# diy_mainboard.net
KiCad netlist of a schematic drawn in EAGLE
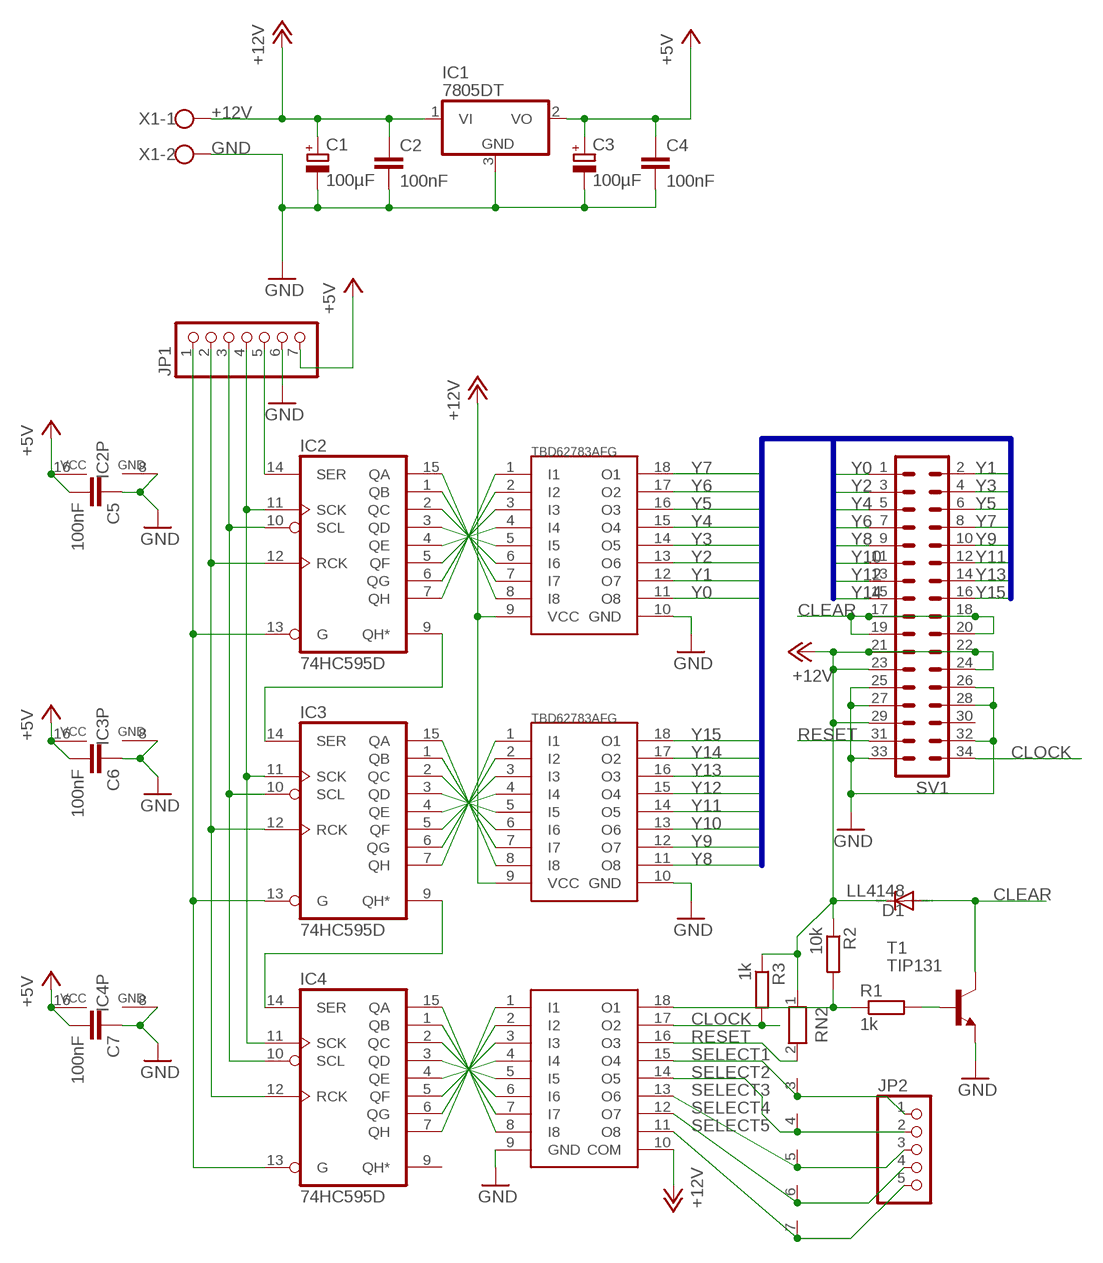
[diagram p0: schematic, sheet 1]

(export (version "E")
  (design (tool "Eeschema 10.0.6"))
  (components
    (comp (ref "C1")
      (value "100µF")
      (footprint "eagle-import:153CLV-0605")
      (libsource (lib "eagle-import") (part "CPOL-EU153CLV-0605"))
    )
    (comp (ref "C2")
      (value "100nF")
      (footprint "eagle-import:C0603")
      (libsource (lib "eagle-import") (part "C-EUC0603"))
    )
    (comp (ref "C3")
      (value "100µF")
      (footprint "eagle-import:153CLV-0605")
      (libsource (lib "eagle-import") (part "CPOL-EU153CLV-0605"))
    )
    (comp (ref "C4")
      (value "100nF")
      (footprint "eagle-import:C0603")
      (libsource (lib "eagle-import") (part "C-EUC0603"))
    )
    (comp (ref "C5")
      (value "100nF")
      (footprint "eagle-import:C0603")
      (libsource (lib "eagle-import") (part "C-EUC0603"))
    )
    (comp (ref "C6")
      (value "100nF")
      (footprint "eagle-import:C0603")
      (libsource (lib "eagle-import") (part "C-EUC0603"))
    )
    (comp (ref "C7")
      (value "100nF")
      (footprint "eagle-import:C0603")
      (libsource (lib "eagle-import") (part "C-EUC0603"))
    )
    (comp (ref "D1")
      (value "LL4148")
      (footprint "eagle-import:SOD80C")
      (libsource (lib "eagle-import") (part "PMLL4150"))
    )
    (comp (ref "IC1")
      (value "7805DT")
      (footprint "eagle-import:TO252")
      (libsource (lib "eagle-import") (part "78DT05"))
    )
    (comp (ref "IC2")
      (value "74HC595D")
      (footprint "eagle-import:SO16")
      (fields (field (name "DIGIKEY") "568-2263-1-ND"))
      (libsource (lib "eagle-import") (part "74595DHC"))
    )
    (comp (ref "IC3")
      (value "74HC595D")
      (footprint "eagle-import:SO16")
      (fields (field (name "DIGIKEY") "568-2263-1-ND"))
      (libsource (lib "eagle-import") (part "74595DHC"))
    )
    (comp (ref "IC4")
      (value "74HC595D")
      (footprint "eagle-import:SO16")
      (fields (field (name "DIGIKEY") "568-2263-1-ND"))
      (libsource (lib "eagle-import") (part "74595DHC"))
    )
    (comp (ref "JP1")
      (value "PINHD-1X7")
      (footprint "eagle-import:1X07")
      (libsource (lib "eagle-import") (part "PINHD-1X7"))
    )
    (comp (ref "JP2")
      (value "PINHD-1X5")
      (footprint "eagle-import:1X05")
      (libsource (lib "eagle-import") (part "PINHD-1X5"))
    )
    (comp (ref "R1")
      (value "1k")
      (footprint "eagle-import:R0805")
      (libsource (lib "eagle-import") (part "R-EU_R0805"))
    )
    (comp (ref "R2")
      (value "10k")
      (footprint "eagle-import:R0805")
      (libsource (lib "eagle-import") (part "R-EU_R0805"))
    )
    (comp (ref "R3")
      (value "1k")
      (footprint "eagle-import:R0805")
      (libsource (lib "eagle-import") (part "R-EU_R0805"))
    )
    (comp (ref "RN2")
      (value "RN06")
      (footprint "eagle-import:RN-7")
      (libsource (lib "eagle-import") (part "RN06"))
    )
    (comp (ref "SV1")
      (value "ML34")
      (footprint "eagle-import:ML34")
      (libsource (lib "eagle-import") (part "ML34"))
    )
    (comp (ref "T1")
      (value "TIP131")
      (footprint "eagle-import:TO220BV")
      (libsource (lib "eagle-import") (part "2SC1306"))
    )
    (comp (ref "U$1")
      (value "TBD62783AFG")
      (footprint "eagle-import:SO8-L")
      (libsource (lib "eagle-import") (part "TBD62783AFG"))
    )
    (comp (ref "U$2")
      (value "TBD62783AFG")
      (footprint "eagle-import:SO8-L")
      (libsource (lib "eagle-import") (part "TBD62783AFG"))
    )
    (comp (ref "U$3")
      (value "ULN2803")
      (footprint "eagle-import:SO8-L")
      (libsource (lib "eagle-import") (part "ULN2803"))
    )
    (comp (ref "X1")
      (value "W237-102")
      (footprint "eagle-import:W237-102")
      (fields (field (name "MPN") "237-102"))
      (libsource (lib "eagle-import") (part "W237-102"))
    )
  )
  (nets
    (net (code "1") (name "+5V") (class "Default")
      (node (ref "C3") (pin "+") (pinfunction "+_+") (pintype "passive"))
      (node (ref "C4") (pin "1") (pinfunction "1_1") (pintype "passive"))
      (node (ref "C5") (pin "2") (pinfunction "2_2") (pintype "passive"))
      (node (ref "C6") (pin "2") (pinfunction "2_2") (pintype "passive"))
      (node (ref "C7") (pin "2") (pinfunction "2_2") (pintype "passive"))
      (node (ref "IC1") (pin "2") (pinfunction "VO_2") (pintype "passive"))
      (node (ref "IC2") (pin "16") (pinfunction "VCC_16") (pintype "power_in"))
      (node (ref "IC3") (pin "16") (pinfunction "VCC_16") (pintype "power_in"))
      (node (ref "IC4") (pin "16") (pinfunction "VCC_16") (pintype "power_in"))
      (node (ref "JP1") (pin "7") (pinfunction "7_7") (pintype "passive"))
    )
    (net (code "2") (name "+12V") (class "Default")
      (node (ref "C1") (pin "+") (pinfunction "+_+") (pintype "passive"))
      (node (ref "C2") (pin "1") (pinfunction "1_1") (pintype "passive"))
      (node (ref "D1") (pin "C") (pinfunction "C_C") (pintype "passive"))
      (node (ref "IC1") (pin "1") (pinfunction "VI_1") (pintype "input"))
      (node (ref "R2") (pin "1") (pinfunction "1_1") (pintype "passive"))
      (node (ref "R3") (pin "1") (pinfunction "1_1") (pintype "passive"))
      (node (ref "RN2") (pin "1") (pinfunction "1_1") (pintype "passive"))
      (node (ref "SV1") (pin "21") (pinfunction "21_21") (pintype "passive"))
      (node (ref "SV1") (pin "22") (pinfunction "22_22") (pintype "passive"))
      (node (ref "SV1") (pin "23") (pinfunction "23_23") (pintype "passive"))
      (node (ref "SV1") (pin "24") (pinfunction "24_24") (pintype "passive"))
      (node (ref "SV1") (pin "29") (pinfunction "29_29") (pintype "passive"))
      (node (ref "U$1") (pin "9") (pinfunction "VCC_9") (pintype "bidirectional"))
      (node (ref "U$2") (pin "9") (pinfunction "VCC_9") (pintype "bidirectional"))
      (node (ref "U$3") (pin "10") (pinfunction "COM_10") (pintype "bidirectional"))
      (node (ref "X1") (pin "1") (pinfunction "KL_1") (pintype "passive"))
    )
    (net (code "3") (name "/CLEAR") (class "Default")
      (node (ref "D1") (pin "A") (pinfunction "A_A") (pintype "passive"))
      (node (ref "SV1") (pin "17") (pinfunction "17_17") (pintype "passive"))
      (node (ref "SV1") (pin "18") (pinfunction "18_18") (pintype "passive"))
      (node (ref "SV1") (pin "19") (pinfunction "19_19") (pintype "passive"))
      (node (ref "SV1") (pin "20") (pinfunction "20_20") (pintype "passive"))
      (node (ref "T1") (pin "2") (pinfunction "C_2") (pintype "passive"))
    )
    (net (code "4") (name "/CLOCK") (class "Default")
      (node (ref "R3") (pin "2") (pinfunction "2_2") (pintype "passive"))
      (node (ref "SV1") (pin "34") (pinfunction "34_34") (pintype "passive"))
      (node (ref "U$3") (pin "17") (pinfunction "O2_17") (pintype "bidirectional"))
    )
    (net (code "5") (name "/RESET") (class "Default")
      (node (ref "RN2") (pin "2") (pinfunction "2_2") (pintype "passive"))
      (node (ref "SV1") (pin "31") (pinfunction "31_31") (pintype "passive"))
      (node (ref "U$3") (pin "16") (pinfunction "O3_16") (pintype "bidirectional"))
    )
    (net (code "6") (name "/SELECT1") (class "Default")
      (node (ref "JP2") (pin "1") (pinfunction "1_1") (pintype "passive"))
      (node (ref "RN2") (pin "3") (pinfunction "3_3") (pintype "passive"))
      (node (ref "U$3") (pin "15") (pinfunction "O4_15") (pintype "bidirectional"))
    )
    (net (code "7") (name "/SELECT2") (class "Default")
      (node (ref "JP2") (pin "2") (pinfunction "2_2") (pintype "passive"))
      (node (ref "RN2") (pin "4") (pinfunction "4_4") (pintype "passive"))
      (node (ref "U$3") (pin "14") (pinfunction "O5_14") (pintype "bidirectional"))
    )
    (net (code "8") (name "/SELECT3") (class "Default")
      (node (ref "JP2") (pin "3") (pinfunction "3_3") (pintype "passive"))
      (node (ref "RN2") (pin "5") (pinfunction "5_5") (pintype "passive"))
      (node (ref "U$3") (pin "13") (pinfunction "O6_13") (pintype "bidirectional"))
    )
    (net (code "9") (name "/SELECT4") (class "Default")
      (node (ref "JP2") (pin "4") (pinfunction "4_4") (pintype "passive"))
      (node (ref "RN2") (pin "6") (pinfunction "6_6") (pintype "passive"))
      (node (ref "U$3") (pin "12") (pinfunction "O7_12") (pintype "bidirectional"))
    )
    (net (code "10") (name "/SELECT5") (class "Default")
      (node (ref "JP2") (pin "5") (pinfunction "5_5") (pintype "passive"))
      (node (ref "RN2") (pin "7") (pinfunction "7_7") (pintype "passive"))
      (node (ref "U$3") (pin "11") (pinfunction "O8_11") (pintype "bidirectional"))
    )
    (net (code "11") (name "/Y0") (class "Default")
      (node (ref "SV1") (pin "1") (pinfunction "1_1") (pintype "passive"))
      (node (ref "U$1") (pin "11") (pinfunction "O8_11") (pintype "bidirectional"))
    )
    (net (code "12") (name "/Y1") (class "Default")
      (node (ref "SV1") (pin "2") (pinfunction "2_2") (pintype "passive"))
      (node (ref "U$1") (pin "12") (pinfunction "O7_12") (pintype "bidirectional"))
    )
    (net (code "13") (name "/Y2") (class "Default")
      (node (ref "SV1") (pin "3") (pinfunction "3_3") (pintype "passive"))
      (node (ref "U$1") (pin "13") (pinfunction "O6_13") (pintype "bidirectional"))
    )
    (net (code "14") (name "/Y3") (class "Default")
      (node (ref "SV1") (pin "4") (pinfunction "4_4") (pintype "passive"))
      (node (ref "U$1") (pin "14") (pinfunction "O5_14") (pintype "bidirectional"))
    )
    (net (code "15") (name "/Y4") (class "Default")
      (node (ref "SV1") (pin "5") (pinfunction "5_5") (pintype "passive"))
      (node (ref "U$1") (pin "15") (pinfunction "O4_15") (pintype "bidirectional"))
    )
    (net (code "16") (name "/Y5") (class "Default")
      (node (ref "SV1") (pin "6") (pinfunction "6_6") (pintype "passive"))
      (node (ref "U$1") (pin "16") (pinfunction "O3_16") (pintype "bidirectional"))
    )
    (net (code "17") (name "/Y6") (class "Default")
      (node (ref "SV1") (pin "7") (pinfunction "7_7") (pintype "passive"))
      (node (ref "U$1") (pin "17") (pinfunction "O2_17") (pintype "bidirectional"))
    )
    (net (code "18") (name "/Y7") (class "Default")
      (node (ref "SV1") (pin "8") (pinfunction "8_8") (pintype "passive"))
      (node (ref "U$1") (pin "18") (pinfunction "O1_18") (pintype "bidirectional"))
    )
    (net (code "19") (name "/Y8") (class "Default")
      (node (ref "SV1") (pin "9") (pinfunction "9_9") (pintype "passive"))
      (node (ref "U$2") (pin "11") (pinfunction "O8_11") (pintype "bidirectional"))
    )
    (net (code "20") (name "/Y9") (class "Default")
      (node (ref "SV1") (pin "10") (pinfunction "10_10") (pintype "passive"))
      (node (ref "U$2") (pin "12") (pinfunction "O7_12") (pintype "bidirectional"))
    )
    (net (code "21") (name "/Y10") (class "Default")
      (node (ref "SV1") (pin "11") (pinfunction "11_11") (pintype "passive"))
      (node (ref "U$2") (pin "13") (pinfunction "O6_13") (pintype "bidirectional"))
    )
    (net (code "22") (name "/Y11") (class "Default")
      (node (ref "SV1") (pin "12") (pinfunction "12_12") (pintype "passive"))
      (node (ref "U$2") (pin "14") (pinfunction "O5_14") (pintype "bidirectional"))
    )
    (net (code "23") (name "/Y12") (class "Default")
      (node (ref "SV1") (pin "13") (pinfunction "13_13") (pintype "passive"))
      (node (ref "U$2") (pin "15") (pinfunction "O4_15") (pintype "bidirectional"))
    )
    (net (code "24") (name "/Y13") (class "Default")
      (node (ref "SV1") (pin "14") (pinfunction "14_14") (pintype "passive"))
      (node (ref "U$2") (pin "16") (pinfunction "O3_16") (pintype "bidirectional"))
    )
    (net (code "25") (name "/Y14") (class "Default")
      (node (ref "SV1") (pin "15") (pinfunction "15_15") (pintype "passive"))
      (node (ref "U$2") (pin "17") (pinfunction "O2_17") (pintype "bidirectional"))
    )
    (net (code "26") (name "/Y15") (class "Default")
      (node (ref "SV1") (pin "16") (pinfunction "16_16") (pintype "passive"))
      (node (ref "U$2") (pin "18") (pinfunction "O1_18") (pintype "bidirectional"))
    )
    (net (code "27") (name "GND") (class "Default")
      (node (ref "C1") (pin "-") (pinfunction "-_-") (pintype "passive"))
      (node (ref "C2") (pin "2") (pinfunction "2_2") (pintype "passive"))
      (node (ref "C3") (pin "-") (pinfunction "-_-") (pintype "passive"))
      (node (ref "C4") (pin "2") (pinfunction "2_2") (pintype "passive"))
      (node (ref "C5") (pin "1") (pinfunction "1_1") (pintype "passive"))
      (node (ref "C6") (pin "1") (pinfunction "1_1") (pintype "passive"))
      (node (ref "C7") (pin "1") (pinfunction "1_1") (pintype "passive"))
      (node (ref "IC1") (pin "3") (pinfunction "GND_3") (pintype "passive"))
      (node (ref "IC2") (pin "8") (pinfunction "GND_8") (pintype "power_in"))
      (node (ref "IC3") (pin "8") (pinfunction "GND_8") (pintype "power_in"))
      (node (ref "IC4") (pin "8") (pinfunction "GND_8") (pintype "power_in"))
      (node (ref "JP1") (pin "6") (pinfunction "6_6") (pintype "passive"))
      (node (ref "SV1") (pin "25") (pinfunction "25_25") (pintype "passive"))
      (node (ref "SV1") (pin "26") (pinfunction "26_26") (pintype "passive"))
      (node (ref "SV1") (pin "27") (pinfunction "27_27") (pintype "passive"))
      (node (ref "SV1") (pin "28") (pinfunction "28_28") (pintype "passive"))
      (node (ref "SV1") (pin "32") (pinfunction "32_32") (pintype "passive"))
      (node (ref "SV1") (pin "33") (pinfunction "33_33") (pintype "passive"))
      (node (ref "T1") (pin "3") (pinfunction "E_3") (pintype "passive"))
      (node (ref "U$1") (pin "10") (pinfunction "GND_10") (pintype "bidirectional"))
      (node (ref "U$2") (pin "10") (pinfunction "GND_10") (pintype "bidirectional"))
      (node (ref "U$3") (pin "9") (pinfunction "GND_9") (pintype "bidirectional"))
      (node (ref "X1") (pin "2") (pinfunction "KL_2") (pintype "passive"))
    )
    (net (code "28") (name "Net-(IC2A-G)") (class "Default")
      (node (ref "IC2") (pin "13") (pinfunction "G_13") (pintype "input"))
      (node (ref "IC3") (pin "13") (pinfunction "G_13") (pintype "input"))
      (node (ref "IC4") (pin "13") (pinfunction "G_13") (pintype "input"))
      (node (ref "JP1") (pin "1") (pinfunction "1_1") (pintype "passive"))
    )
    (net (code "29") (name "Net-(IC2A-QA)") (class "Default")
      (node (ref "IC2") (pin "15") (pinfunction "QA_15") (pintype "tri_state"))
      (node (ref "U$1") (pin "8") (pinfunction "I8_8") (pintype "bidirectional"))
    )
    (net (code "30") (name "Net-(IC2A-QB)") (class "Default")
      (node (ref "IC2") (pin "1") (pinfunction "QB_1") (pintype "tri_state"))
      (node (ref "U$1") (pin "7") (pinfunction "I7_7") (pintype "bidirectional"))
    )
    (net (code "31") (name "Net-(IC2A-QC)") (class "Default")
      (node (ref "IC2") (pin "2") (pinfunction "QC_2") (pintype "tri_state"))
      (node (ref "U$1") (pin "6") (pinfunction "I6_6") (pintype "bidirectional"))
    )
    (net (code "32") (name "Net-(IC2A-QD)") (class "Default")
      (node (ref "IC2") (pin "3") (pinfunction "QD_3") (pintype "tri_state"))
      (node (ref "U$1") (pin "5") (pinfunction "I5_5") (pintype "bidirectional"))
    )
    (net (code "33") (name "Net-(IC2A-QE)") (class "Default")
      (node (ref "IC2") (pin "4") (pinfunction "QE_4") (pintype "tri_state"))
      (node (ref "U$1") (pin "4") (pinfunction "I4_4") (pintype "bidirectional"))
    )
    (net (code "34") (name "Net-(IC2A-QF)") (class "Default")
      (node (ref "IC2") (pin "5") (pinfunction "QF_5") (pintype "tri_state"))
      (node (ref "U$1") (pin "3") (pinfunction "I3_3") (pintype "bidirectional"))
    )
    (net (code "35") (name "Net-(IC2A-QG)") (class "Default")
      (node (ref "IC2") (pin "6") (pinfunction "QG_6") (pintype "tri_state"))
      (node (ref "U$1") (pin "2") (pinfunction "I2_2") (pintype "bidirectional"))
    )
    (net (code "36") (name "Net-(IC2A-QH)") (class "Default")
      (node (ref "IC2") (pin "7") (pinfunction "QH_7") (pintype "tri_state"))
      (node (ref "U$1") (pin "1") (pinfunction "I1_1") (pintype "bidirectional"))
    )
    (net (code "37") (name "Net-(IC2A-QH*)") (class "Default")
      (node (ref "IC2") (pin "9") (pinfunction "QH*_9") (pintype "tri_state"))
      (node (ref "IC3") (pin "14") (pinfunction "SER_14") (pintype "input"))
    )
    (net (code "38") (name "Net-(IC2A-RCK)") (class "Default")
      (node (ref "IC2") (pin "12") (pinfunction "RCK_12") (pintype "input"))
      (node (ref "IC3") (pin "12") (pinfunction "RCK_12") (pintype "input"))
      (node (ref "IC4") (pin "12") (pinfunction "RCK_12") (pintype "input"))
      (node (ref "JP1") (pin "2") (pinfunction "2_2") (pintype "passive"))
    )
    (net (code "39") (name "Net-(IC2A-SCK)") (class "Default")
      (node (ref "IC2") (pin "11") (pinfunction "SCK_11") (pintype "input"))
      (node (ref "IC3") (pin "11") (pinfunction "SCK_11") (pintype "input"))
      (node (ref "IC4") (pin "11") (pinfunction "SCK_11") (pintype "input"))
      (node (ref "JP1") (pin "4") (pinfunction "4_4") (pintype "passive"))
    )
    (net (code "40") (name "Net-(IC2A-SCL)") (class "Default")
      (node (ref "IC2") (pin "10") (pinfunction "SCL_10") (pintype "input"))
      (node (ref "IC3") (pin "10") (pinfunction "SCL_10") (pintype "input"))
      (node (ref "IC4") (pin "10") (pinfunction "SCL_10") (pintype "input"))
      (node (ref "JP1") (pin "3") (pinfunction "3_3") (pintype "passive"))
    )
    (net (code "41") (name "Net-(IC2A-SER)") (class "Default")
      (node (ref "IC2") (pin "14") (pinfunction "SER_14") (pintype "input"))
      (node (ref "JP1") (pin "5") (pinfunction "5_5") (pintype "passive"))
    )
    (net (code "42") (name "Net-(IC3A-QA)") (class "Default")
      (node (ref "IC3") (pin "15") (pinfunction "QA_15") (pintype "tri_state"))
      (node (ref "U$2") (pin "8") (pinfunction "I8_8") (pintype "bidirectional"))
    )
    (net (code "43") (name "Net-(IC3A-QB)") (class "Default")
      (node (ref "IC3") (pin "1") (pinfunction "QB_1") (pintype "tri_state"))
      (node (ref "U$2") (pin "7") (pinfunction "I7_7") (pintype "bidirectional"))
    )
    (net (code "44") (name "Net-(IC3A-QC)") (class "Default")
      (node (ref "IC3") (pin "2") (pinfunction "QC_2") (pintype "tri_state"))
      (node (ref "U$2") (pin "6") (pinfunction "I6_6") (pintype "bidirectional"))
    )
    (net (code "45") (name "Net-(IC3A-QD)") (class "Default")
      (node (ref "IC3") (pin "3") (pinfunction "QD_3") (pintype "tri_state"))
      (node (ref "U$2") (pin "5") (pinfunction "I5_5") (pintype "bidirectional"))
    )
    (net (code "46") (name "Net-(IC3A-QE)") (class "Default")
      (node (ref "IC3") (pin "4") (pinfunction "QE_4") (pintype "tri_state"))
      (node (ref "U$2") (pin "4") (pinfunction "I4_4") (pintype "bidirectional"))
    )
    (net (code "47") (name "Net-(IC3A-QF)") (class "Default")
      (node (ref "IC3") (pin "5") (pinfunction "QF_5") (pintype "tri_state"))
      (node (ref "U$2") (pin "3") (pinfunction "I3_3") (pintype "bidirectional"))
    )
    (net (code "48") (name "Net-(IC3A-QG)") (class "Default")
      (node (ref "IC3") (pin "6") (pinfunction "QG_6") (pintype "tri_state"))
      (node (ref "U$2") (pin "2") (pinfunction "I2_2") (pintype "bidirectional"))
    )
    (net (code "49") (name "Net-(IC3A-QH)") (class "Default")
      (node (ref "IC3") (pin "7") (pinfunction "QH_7") (pintype "tri_state"))
      (node (ref "U$2") (pin "1") (pinfunction "I1_1") (pintype "bidirectional"))
    )
    (net (code "50") (name "Net-(IC3A-QH*)") (class "Default")
      (node (ref "IC3") (pin "9") (pinfunction "QH*_9") (pintype "tri_state"))
      (node (ref "IC4") (pin "14") (pinfunction "SER_14") (pintype "input"))
    )
    (net (code "51") (name "Net-(IC4A-QA)") (class "Default")
      (node (ref "IC4") (pin "15") (pinfunction "QA_15") (pintype "tri_state"))
      (node (ref "U$3") (pin "8") (pinfunction "I8_8") (pintype "bidirectional"))
    )
    (net (code "52") (name "Net-(IC4A-QB)") (class "Default")
      (node (ref "IC4") (pin "1") (pinfunction "QB_1") (pintype "tri_state"))
      (node (ref "U$3") (pin "7") (pinfunction "I7_7") (pintype "bidirectional"))
    )
    (net (code "53") (name "Net-(IC4A-QC)") (class "Default")
      (node (ref "IC4") (pin "2") (pinfunction "QC_2") (pintype "tri_state"))
      (node (ref "U$3") (pin "6") (pinfunction "I6_6") (pintype "bidirectional"))
    )
    (net (code "54") (name "Net-(IC4A-QD)") (class "Default")
      (node (ref "IC4") (pin "3") (pinfunction "QD_3") (pintype "tri_state"))
      (node (ref "U$3") (pin "5") (pinfunction "I5_5") (pintype "bidirectional"))
    )
    (net (code "55") (name "Net-(IC4A-QE)") (class "Default")
      (node (ref "IC4") (pin "4") (pinfunction "QE_4") (pintype "tri_state"))
      (node (ref "U$3") (pin "4") (pinfunction "I4_4") (pintype "bidirectional"))
    )
    (net (code "56") (name "Net-(IC4A-QF)") (class "Default")
      (node (ref "IC4") (pin "5") (pinfunction "QF_5") (pintype "tri_state"))
      (node (ref "U$3") (pin "3") (pinfunction "I3_3") (pintype "bidirectional"))
    )
    (net (code "57") (name "Net-(IC4A-QG)") (class "Default")
      (node (ref "IC4") (pin "6") (pinfunction "QG_6") (pintype "tri_state"))
      (node (ref "U$3") (pin "2") (pinfunction "I2_2") (pintype "bidirectional"))
    )
    (net (code "58") (name "Net-(IC4A-QH)") (class "Default")
      (node (ref "IC4") (pin "7") (pinfunction "QH_7") (pintype "tri_state"))
      (node (ref "U$3") (pin "1") (pinfunction "I1_1") (pintype "bidirectional"))
    )
    (net (code "59") (name "Net-(T1-B)") (class "Default")
      (node (ref "R1") (pin "2") (pinfunction "2_2") (pintype "passive"))
      (node (ref "T1") (pin "1") (pinfunction "B_1") (pintype "passive"))
    )
    (net (code "60") (name "Net-(U$3-O1)") (class "Default")
      (node (ref "R1") (pin "1") (pinfunction "1_1") (pintype "passive"))
      (node (ref "R2") (pin "2") (pinfunction "2_2") (pintype "passive"))
      (node (ref "U$3") (pin "18") (pinfunction "O1_18") (pintype "bidirectional"))
    )
    (net (code "61") (name "unconnected-(IC4A-QH*-Pad9)") (class "Default")
      (node (ref "IC4") (pin "9") (pinfunction "QH*_9") (pintype "tri_state"))
    )
    (net (code "62") (name "unconnected-(SV1-Pad30)") (class "Default")
      (node (ref "SV1") (pin "30") (pinfunction "30_30") (pintype "passive"))
    )
  )
)
